# MECHANICAL.net
KiCad netlist of a schematic drawn in Altium Designer
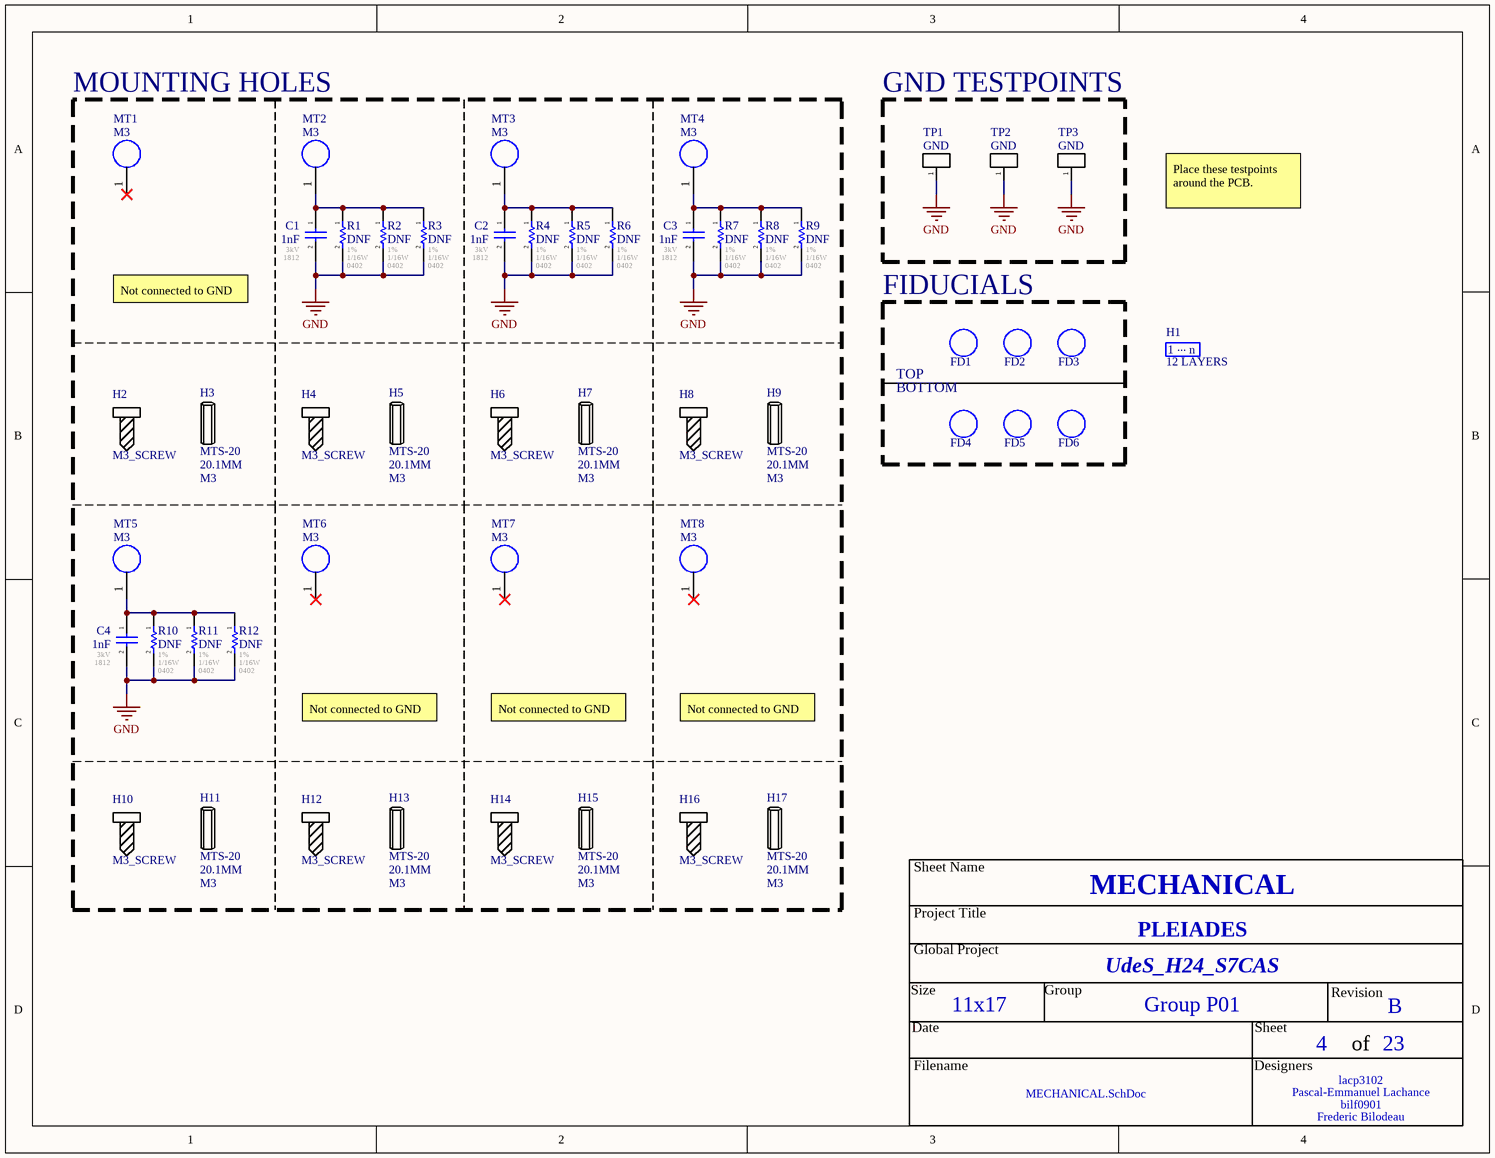
[diagram p0: MECHANICAL.SchDoc]

(export (version "E")
  (design (tool "Eeschema 10.0.6"))
  (components
    (comp (ref "C1")
      (value "1nF")
      (footprint "1812")
      (description "C1812C102KHRACAUTO\r\n0402 470pF 10% X7R Ceramic Capacitor")
      (fields
        (field (name "MFR") "KEMET")
        (field (name "PART#") "C1812C102KHRACAUTO")
        (field (name "VOLTAGE - RATED") "3kV")
      )
      (libsource (lib "Symbols") (part "CAP_CER"))
    )
    (comp (ref "C2")
      (value "1nF")
      (footprint "1812")
      (description "C1812C102KHRACAUTO\r\n0402 470pF 10% X7R Ceramic Capacitor")
      (fields
        (field (name "MFR") "KEMET")
        (field (name "PART#") "C1812C102KHRACAUTO")
        (field (name "VOLTAGE - RATED") "3kV")
      )
      (libsource (lib "Symbols") (part "CAP_CER"))
    )
    (comp (ref "C3")
      (value "1nF")
      (footprint "1812")
      (description "C1812C102KHRACAUTO\r\n0402 470pF 10% X7R Ceramic Capacitor")
      (fields
        (field (name "MFR") "KEMET")
        (field (name "PART#") "C1812C102KHRACAUTO")
        (field (name "VOLTAGE - RATED") "3kV")
      )
      (libsource (lib "Symbols") (part "CAP_CER"))
    )
    (comp (ref "C4")
      (value "1nF")
      (footprint "1812")
      (description "C1812C102KHRACAUTO\r\n0402 470pF 10% X7R Ceramic Capacitor")
      (fields
        (field (name "MFR") "KEMET")
        (field (name "PART#") "C1812C102KHRACAUTO")
        (field (name "VOLTAGE - RATED") "3kV")
      )
      (libsource (lib "Symbols") (part "CAP_CER"))
    )
    (comp (ref "FD1") (value "FIDUCIAL") (footprint "FIDUCIAL") (libsource (lib "Symbols") (part "FIDUCIAL")))
    (comp (ref "FD2") (value "FIDUCIAL") (footprint "FIDUCIAL") (libsource (lib "Symbols") (part "FIDUCIAL")))
    (comp (ref "FD3") (value "FIDUCIAL") (footprint "FIDUCIAL") (libsource (lib "Symbols") (part "FIDUCIAL")))
    (comp (ref "FD4") (value "FIDUCIAL") (footprint "FIDUCIAL") (libsource (lib "Symbols") (part "FIDUCIAL")))
    (comp (ref "FD5") (value "FIDUCIAL") (footprint "FIDUCIAL") (libsource (lib "Symbols") (part "FIDUCIAL")))
    (comp (ref "FD6") (value "FIDUCIAL") (footprint "FIDUCIAL") (libsource (lib "Symbols") (part "FIDUCIAL")))
    (comp (ref "H1")
      (value "12 LAYERS")
      (footprint "LAYERS_12")
      (libsource (lib "Misc") (part "MECH_LAYER_MARKER"))
    )
    (comp (ref "H2") (value "M3_SCREW") (libsource (lib "Misc") (part "M3_screw")))
    (comp (ref "H3")
      (value "MTS-20")
      (footprint "STANDOFF_MTS-20")
      (fields (field (name "LENGTH") "20.1MM") (field (name "THREAD SIZE") "M3"))
      (libsource (lib "Misc") (part "M3_STANDOFF"))
    )
    (comp (ref "H4") (value "M3_SCREW") (libsource (lib "Misc") (part "M3_screw")))
    (comp (ref "H5")
      (value "MTS-20")
      (footprint "STANDOFF_MTS-20")
      (fields (field (name "LENGTH") "20.1MM") (field (name "THREAD SIZE") "M3"))
      (libsource (lib "Misc") (part "M3_STANDOFF"))
    )
    (comp (ref "H6") (value "M3_SCREW") (libsource (lib "Misc") (part "M3_screw")))
    (comp (ref "H7")
      (value "MTS-20")
      (footprint "STANDOFF_MTS-20")
      (fields (field (name "LENGTH") "20.1MM") (field (name "THREAD SIZE") "M3"))
      (libsource (lib "Misc") (part "M3_STANDOFF"))
    )
    (comp (ref "H8") (value "M3_SCREW") (libsource (lib "Misc") (part "M3_screw")))
    (comp (ref "H9")
      (value "MTS-20")
      (footprint "STANDOFF_MTS-20")
      (fields (field (name "LENGTH") "20.1MM") (field (name "THREAD SIZE") "M3"))
      (libsource (lib "Misc") (part "M3_STANDOFF"))
    )
    (comp (ref "H10") (value "M3_SCREW") (libsource (lib "Misc") (part "M3_screw")))
    (comp (ref "H11")
      (value "MTS-20")
      (footprint "STANDOFF_MTS-20")
      (fields (field (name "LENGTH") "20.1MM") (field (name "THREAD SIZE") "M3"))
      (libsource (lib "Misc") (part "M3_STANDOFF"))
    )
    (comp (ref "H12") (value "M3_SCREW") (libsource (lib "Misc") (part "M3_screw")))
    (comp (ref "H13")
      (value "MTS-20")
      (footprint "STANDOFF_MTS-20")
      (fields (field (name "LENGTH") "20.1MM") (field (name "THREAD SIZE") "M3"))
      (libsource (lib "Misc") (part "M3_STANDOFF"))
    )
    (comp (ref "H14") (value "M3_SCREW") (libsource (lib "Misc") (part "M3_screw")))
    (comp (ref "H15")
      (value "MTS-20")
      (footprint "STANDOFF_MTS-20")
      (fields (field (name "LENGTH") "20.1MM") (field (name "THREAD SIZE") "M3"))
      (libsource (lib "Misc") (part "M3_STANDOFF"))
    )
    (comp (ref "H16") (value "M3_SCREW") (libsource (lib "Misc") (part "M3_screw")))
    (comp (ref "H17")
      (value "MTS-20")
      (footprint "STANDOFF_MTS-20")
      (fields (field (name "LENGTH") "20.1MM") (field (name "THREAD SIZE") "M3"))
      (libsource (lib "Misc") (part "M3_STANDOFF"))
    )
    (comp (ref "MT1") (value "M3") (footprint "MTH_M3") (libsource (lib "RaesLib") (part "MOUNTING_HOLE")))
    (comp (ref "MT2") (value "M3") (footprint "MTH_M3") (libsource (lib "RaesLib") (part "MOUNTING_HOLE")))
    (comp (ref "MT3") (value "M3") (footprint "MTH_M3") (libsource (lib "RaesLib") (part "MOUNTING_HOLE")))
    (comp (ref "MT4") (value "M3") (footprint "MTH_M3") (libsource (lib "RaesLib") (part "MOUNTING_HOLE")))
    (comp (ref "MT5") (value "M3") (footprint "MTH_M3") (libsource (lib "RaesLib") (part "MOUNTING_HOLE")))
    (comp (ref "MT6") (value "M3") (footprint "MTH_M3") (libsource (lib "RaesLib") (part "MOUNTING_HOLE")))
    (comp (ref "MT7") (value "M3") (footprint "MTH_M3") (libsource (lib "RaesLib") (part "MOUNTING_HOLE")))
    (comp (ref "MT8") (value "M3") (footprint "MTH_M3") (libsource (lib "RaesLib") (part "MOUNTING_HOLE")))
    (comp (ref "R1")
      (value "DNF")
      (footprint "RES_0402")
      (fields
        (field (name "TOLERANCE") "1%")
        (field (name "POWER") "1/16W")
        (field (name "PACKAGE / CASE") "0402")
      )
      (libsource (lib "Symbols") (part "RESISTOR"))
    )
    (comp (ref "R2")
      (value "DNF")
      (footprint "RES_0402")
      (fields
        (field (name "TOLERANCE") "1%")
        (field (name "POWER") "1/16W")
        (field (name "PACKAGE / CASE") "0402")
      )
      (libsource (lib "Symbols") (part "RESISTOR"))
    )
    (comp (ref "R3")
      (value "DNF")
      (footprint "RES_0402")
      (fields
        (field (name "TOLERANCE") "1%")
        (field (name "POWER") "1/16W")
        (field (name "PACKAGE / CASE") "0402")
      )
      (libsource (lib "Symbols") (part "RESISTOR"))
    )
    (comp (ref "R4")
      (value "DNF")
      (footprint "RES_0402")
      (fields
        (field (name "TOLERANCE") "1%")
        (field (name "POWER") "1/16W")
        (field (name "PACKAGE / CASE") "0402")
      )
      (libsource (lib "Symbols") (part "RESISTOR"))
    )
    (comp (ref "R5")
      (value "DNF")
      (footprint "RES_0402")
      (fields
        (field (name "TOLERANCE") "1%")
        (field (name "POWER") "1/16W")
        (field (name "PACKAGE / CASE") "0402")
      )
      (libsource (lib "Symbols") (part "RESISTOR"))
    )
    (comp (ref "R6")
      (value "DNF")
      (footprint "RES_0402")
      (fields
        (field (name "TOLERANCE") "1%")
        (field (name "POWER") "1/16W")
        (field (name "PACKAGE / CASE") "0402")
      )
      (libsource (lib "Symbols") (part "RESISTOR"))
    )
    (comp (ref "R7")
      (value "DNF")
      (footprint "RES_0402")
      (fields
        (field (name "TOLERANCE") "1%")
        (field (name "POWER") "1/16W")
        (field (name "PACKAGE / CASE") "0402")
      )
      (libsource (lib "Symbols") (part "RESISTOR"))
    )
    (comp (ref "R8")
      (value "DNF")
      (footprint "RES_0402")
      (fields
        (field (name "TOLERANCE") "1%")
        (field (name "POWER") "1/16W")
        (field (name "PACKAGE / CASE") "0402")
      )
      (libsource (lib "Symbols") (part "RESISTOR"))
    )
    (comp (ref "R9")
      (value "DNF")
      (footprint "RES_0402")
      (fields
        (field (name "TOLERANCE") "1%")
        (field (name "POWER") "1/16W")
        (field (name "PACKAGE / CASE") "0402")
      )
      (libsource (lib "Symbols") (part "RESISTOR"))
    )
    (comp (ref "R10")
      (value "DNF")
      (footprint "RES_0402")
      (fields
        (field (name "TOLERANCE") "1%")
        (field (name "POWER") "1/16W")
        (field (name "PACKAGE / CASE") "0402")
      )
      (libsource (lib "Symbols") (part "RESISTOR"))
    )
    (comp (ref "R11")
      (value "DNF")
      (footprint "RES_0402")
      (fields
        (field (name "TOLERANCE") "1%")
        (field (name "POWER") "1/16W")
        (field (name "PACKAGE / CASE") "0402")
      )
      (libsource (lib "Symbols") (part "RESISTOR"))
    )
    (comp (ref "R12")
      (value "DNF")
      (footprint "RES_0402")
      (fields
        (field (name "TOLERANCE") "1%")
        (field (name "POWER") "1/16W")
        (field (name "PACKAGE / CASE") "0402")
      )
      (libsource (lib "Symbols") (part "RESISTOR"))
    )
    (comp (ref "TP1")
      (value "GND")
      (footprint "TP_HOLE")
      (description "Test Point")
      (libsource (lib "Symbols") (part "TESTPOINT"))
    )
    (comp (ref "TP2")
      (value "GND")
      (footprint "TP_HOLE")
      (description "Test Point")
      (libsource (lib "Symbols") (part "TESTPOINT"))
    )
    (comp (ref "TP3")
      (value "GND")
      (footprint "TP_HOLE")
      (description "Test Point")
      (libsource (lib "Symbols") (part "TESTPOINT"))
    )
  )
  (nets
    (net (code "1") (name "GND") (class "Default")
      (node (ref "C1") (pin "2") (pinfunction "2_2") (pintype "passive"))
      (node (ref "C2") (pin "2") (pinfunction "2_2") (pintype "passive"))
      (node (ref "C3") (pin "2") (pinfunction "2_2") (pintype "passive"))
      (node (ref "C4") (pin "2") (pinfunction "2_2") (pintype "passive"))
      (node (ref "R1") (pin "2") (pinfunction "2_2") (pintype "passive"))
      (node (ref "R10") (pin "2") (pinfunction "2_2") (pintype "passive"))
      (node (ref "R11") (pin "2") (pinfunction "2_2") (pintype "passive"))
      (node (ref "R12") (pin "2") (pinfunction "2_2") (pintype "passive"))
      (node (ref "R2") (pin "2") (pinfunction "2_2") (pintype "passive"))
      (node (ref "R3") (pin "2") (pinfunction "2_2") (pintype "passive"))
      (node (ref "R4") (pin "2") (pinfunction "2_2") (pintype "passive"))
      (node (ref "R5") (pin "2") (pinfunction "2_2") (pintype "passive"))
      (node (ref "R6") (pin "2") (pinfunction "2_2") (pintype "passive"))
      (node (ref "R7") (pin "2") (pinfunction "2_2") (pintype "passive"))
      (node (ref "R8") (pin "2") (pinfunction "2_2") (pintype "passive"))
      (node (ref "R9") (pin "2") (pinfunction "2_2") (pintype "passive"))
      (node (ref "TP1") (pin "1") (pinfunction "A_1") (pintype "passive"))
      (node (ref "TP2") (pin "1") (pinfunction "A_1") (pintype "passive"))
      (node (ref "TP3") (pin "1") (pinfunction "A_1") (pintype "passive"))
    )
    (net (code "2") (name "Net-(C1-Pad1)") (class "Default")
      (node (ref "C1") (pin "1") (pinfunction "1_1") (pintype "passive"))
      (node (ref "MT2") (pin "1") (pintype "passive"))
      (node (ref "R1") (pin "1") (pinfunction "1_1") (pintype "passive"))
      (node (ref "R2") (pin "1") (pinfunction "1_1") (pintype "passive"))
      (node (ref "R3") (pin "1") (pinfunction "1_1") (pintype "passive"))
    )
    (net (code "3") (name "Net-(C2-Pad1)") (class "Default")
      (node (ref "C2") (pin "1") (pinfunction "1_1") (pintype "passive"))
      (node (ref "MT3") (pin "1") (pintype "passive"))
      (node (ref "R4") (pin "1") (pinfunction "1_1") (pintype "passive"))
      (node (ref "R5") (pin "1") (pinfunction "1_1") (pintype "passive"))
      (node (ref "R6") (pin "1") (pinfunction "1_1") (pintype "passive"))
    )
    (net (code "4") (name "Net-(C3-Pad1)") (class "Default")
      (node (ref "C3") (pin "1") (pinfunction "1_1") (pintype "passive"))
      (node (ref "MT4") (pin "1") (pintype "passive"))
      (node (ref "R7") (pin "1") (pinfunction "1_1") (pintype "passive"))
      (node (ref "R8") (pin "1") (pinfunction "1_1") (pintype "passive"))
      (node (ref "R9") (pin "1") (pinfunction "1_1") (pintype "passive"))
    )
    (net (code "5") (name "Net-(C4-Pad1)") (class "Default")
      (node (ref "C4") (pin "1") (pinfunction "1_1") (pintype "passive"))
      (node (ref "MT5") (pin "1") (pintype "passive"))
      (node (ref "R10") (pin "1") (pinfunction "1_1") (pintype "passive"))
      (node (ref "R11") (pin "1") (pinfunction "1_1") (pintype "passive"))
      (node (ref "R12") (pin "1") (pinfunction "1_1") (pintype "passive"))
    )
    (net (code "6") (name "unconnected-(MT1-Pad1)") (class "Default")
      (node (ref "MT1") (pin "1") (pintype "passive+no_connect"))
    )
    (net (code "7") (name "unconnected-(MT6-Pad1)") (class "Default")
      (node (ref "MT6") (pin "1") (pintype "passive+no_connect"))
    )
    (net (code "8") (name "unconnected-(MT7-Pad1)") (class "Default")
      (node (ref "MT7") (pin "1") (pintype "passive+no_connect"))
    )
    (net (code "9") (name "unconnected-(MT8-Pad1)") (class "Default")
      (node (ref "MT8") (pin "1") (pintype "passive+no_connect"))
    )
  )
)
